# PCB_Headers.net
KiCad netlist of a schematic drawn in Altium Designer
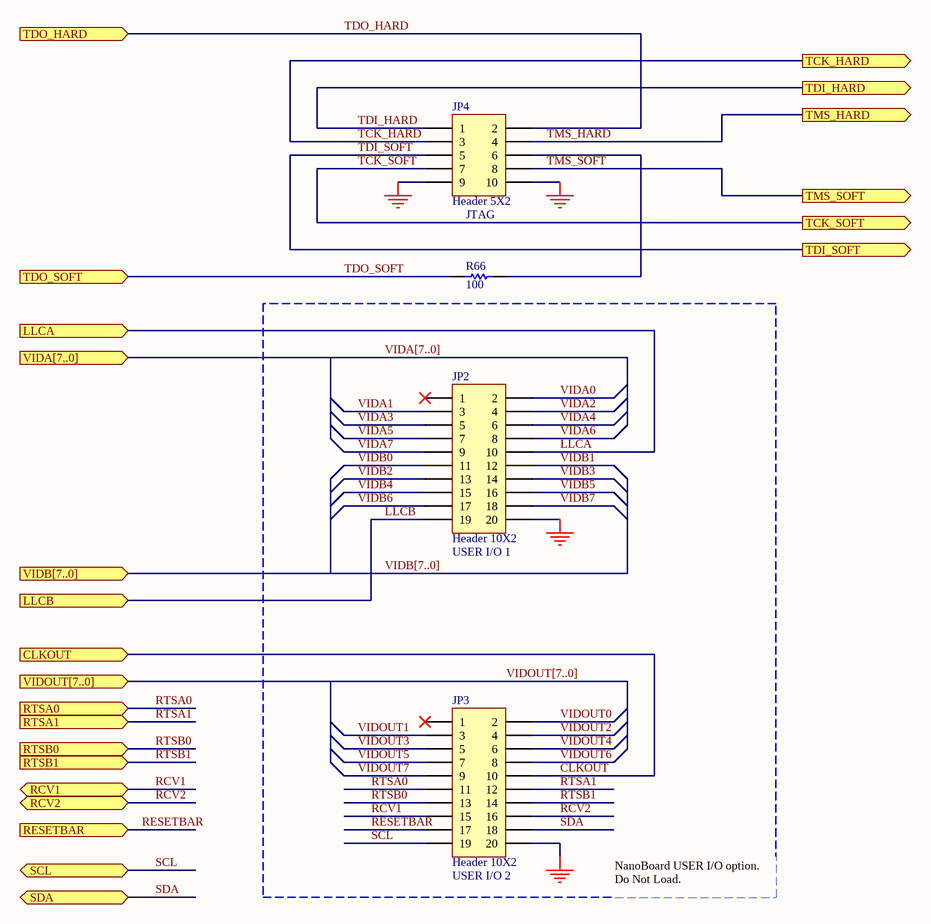
[diagram p0: PCB_Headers.SchDoc]

(export (version "E")
  (design (tool "Eeschema 10.0.6"))
  (components
    (comp (ref "JP2")
      (value "Header 10X2")
      (footprint "HDR2X10")
      (description "Header, 10-Pin, Dual row")
      (fields (field (name "MANUFACTURER") "Generic Components") (field (name "PUBLISHER") "Altium Limited"))
      (libsource (lib "Miscellaneous Connectors") (part "Header 10X2"))
    )
    (comp (ref "JP3")
      (value "Header 10X2")
      (footprint "HDR2X10")
      (description "Header, 10-Pin, Dual row")
      (fields (field (name "MANUFACTURER") "Generic Components") (field (name "PUBLISHER") "Altium Limited"))
      (libsource (lib "Miscellaneous Connectors") (part "Header 10X2"))
    )
    (comp (ref "JP4")
      (value "Header 5X2")
      (footprint "HDR2X5")
      (description "Header, 5-Pin, Dual row")
      (fields (field (name "MANUFACTURER") "Generic Components") (field (name "PUBLISHER") "Altium Limited"))
      (libsource (lib "Miscellaneous Connectors") (part "Header 5X2"))
    )
    (comp (ref "R66")
      (value "100")
      (footprint "PCB_Footprints:CC2012-0805")
      (description "Resistor")
      (libsource (lib "PCB_Symbols") (part "RES"))
    )
  )
  (nets
    (net (code "1") (name "/CLKOUT") (class "Default")
      (node (ref "JP3") (pin "10") (pinfunction "10_10") (pintype "passive"))
    )
    (net (code "2") (name "/LLCA") (class "Default")
      (node (ref "JP2") (pin "10") (pinfunction "10_10") (pintype "passive"))
    )
    (net (code "3") (name "/LLCB") (class "Default")
      (node (ref "JP2") (pin "19") (pinfunction "19_19") (pintype "passive"))
    )
    (net (code "4") (name "/RCV1") (class "Default")
      (node (ref "JP3") (pin "15") (pinfunction "15_15") (pintype "passive"))
    )
    (net (code "5") (name "/RCV2") (class "Default")
      (node (ref "JP3") (pin "16") (pinfunction "16_16") (pintype "passive"))
    )
    (net (code "6") (name "/RESETBAR") (class "Default")
      (node (ref "JP3") (pin "17") (pinfunction "17_17") (pintype "passive"))
    )
    (net (code "7") (name "/RTSA0") (class "Default")
      (node (ref "JP3") (pin "11") (pinfunction "11_11") (pintype "passive"))
    )
    (net (code "8") (name "/RTSA1") (class "Default")
      (node (ref "JP3") (pin "12") (pinfunction "12_12") (pintype "passive"))
    )
    (net (code "9") (name "/RTSB0") (class "Default")
      (node (ref "JP3") (pin "13") (pinfunction "13_13") (pintype "passive"))
    )
    (net (code "10") (name "/RTSB1") (class "Default")
      (node (ref "JP3") (pin "14") (pinfunction "14_14") (pintype "passive"))
    )
    (net (code "11") (name "/SCL") (class "Default")
      (node (ref "JP3") (pin "19") (pinfunction "19_19") (pintype "passive"))
    )
    (net (code "12") (name "/SDA") (class "Default")
      (node (ref "JP3") (pin "18") (pinfunction "18_18") (pintype "passive"))
    )
    (net (code "13") (name "/TCK_HARD") (class "Default")
      (node (ref "JP4") (pin "3") (pinfunction "3_3") (pintype "passive"))
    )
    (net (code "14") (name "/TCK_SOFT") (class "Default")
      (node (ref "JP4") (pin "7") (pinfunction "7_7") (pintype "passive"))
    )
    (net (code "15") (name "/TDI_HARD") (class "Default")
      (node (ref "JP4") (pin "1") (pinfunction "1_1") (pintype "passive"))
    )
    (net (code "16") (name "/TDI_SOFT") (class "Default")
      (node (ref "JP4") (pin "5") (pinfunction "5_5") (pintype "passive"))
    )
    (net (code "17") (name "/TDO_HARD") (class "Default")
      (node (ref "JP4") (pin "2") (pinfunction "2_2") (pintype "passive"))
    )
    (net (code "18") (name "/TDO_SOFT") (class "Default")
      (node (ref "R66") (pin "1") (pinfunction "1_1") (pintype "passive"))
    )
    (net (code "19") (name "/TMS_HARD") (class "Default")
      (node (ref "JP4") (pin "4") (pinfunction "4_4") (pintype "passive"))
    )
    (net (code "20") (name "/TMS_SOFT") (class "Default")
      (node (ref "JP4") (pin "8") (pinfunction "8_8") (pintype "passive"))
    )
    (net (code "21") (name "/VIDA0") (class "Default")
      (node (ref "JP2") (pin "2") (pinfunction "2_2") (pintype "passive"))
    )
    (net (code "22") (name "/VIDA1") (class "Default")
      (node (ref "JP2") (pin "3") (pinfunction "3_3") (pintype "passive"))
    )
    (net (code "23") (name "/VIDA2") (class "Default")
      (node (ref "JP2") (pin "4") (pinfunction "4_4") (pintype "passive"))
    )
    (net (code "24") (name "/VIDA3") (class "Default")
      (node (ref "JP2") (pin "5") (pinfunction "5_5") (pintype "passive"))
    )
    (net (code "25") (name "/VIDA4") (class "Default")
      (node (ref "JP2") (pin "6") (pinfunction "6_6") (pintype "passive"))
    )
    (net (code "26") (name "/VIDA5") (class "Default")
      (node (ref "JP2") (pin "7") (pinfunction "7_7") (pintype "passive"))
    )
    (net (code "27") (name "/VIDA6") (class "Default")
      (node (ref "JP2") (pin "8") (pinfunction "8_8") (pintype "passive"))
    )
    (net (code "28") (name "/VIDA7") (class "Default")
      (node (ref "JP2") (pin "9") (pinfunction "9_9") (pintype "passive"))
    )
    (net (code "30") (name "/VIDB0") (class "Default")
      (node (ref "JP2") (pin "11") (pinfunction "11_11") (pintype "passive"))
    )
    (net (code "31") (name "/VIDB1") (class "Default")
      (node (ref "JP2") (pin "12") (pinfunction "12_12") (pintype "passive"))
    )
    (net (code "32") (name "/VIDB2") (class "Default")
      (node (ref "JP2") (pin "13") (pinfunction "13_13") (pintype "passive"))
    )
    (net (code "33") (name "/VIDB3") (class "Default")
      (node (ref "JP2") (pin "14") (pinfunction "14_14") (pintype "passive"))
    )
    (net (code "34") (name "/VIDB4") (class "Default")
      (node (ref "JP2") (pin "15") (pinfunction "15_15") (pintype "passive"))
    )
    (net (code "35") (name "/VIDB5") (class "Default")
      (node (ref "JP2") (pin "16") (pinfunction "16_16") (pintype "passive"))
    )
    (net (code "36") (name "/VIDB6") (class "Default")
      (node (ref "JP2") (pin "17") (pinfunction "17_17") (pintype "passive"))
    )
    (net (code "37") (name "/VIDB7") (class "Default")
      (node (ref "JP2") (pin "18") (pinfunction "18_18") (pintype "passive"))
    )
    (net (code "39") (name "/VIDOUT0") (class "Default")
      (node (ref "JP3") (pin "2") (pinfunction "2_2") (pintype "passive"))
    )
    (net (code "40") (name "/VIDOUT1") (class "Default")
      (node (ref "JP3") (pin "3") (pinfunction "3_3") (pintype "passive"))
    )
    (net (code "41") (name "/VIDOUT2") (class "Default")
      (node (ref "JP3") (pin "4") (pinfunction "4_4") (pintype "passive"))
    )
    (net (code "42") (name "/VIDOUT3") (class "Default")
      (node (ref "JP3") (pin "5") (pinfunction "5_5") (pintype "passive"))
    )
    (net (code "43") (name "/VIDOUT4") (class "Default")
      (node (ref "JP3") (pin "6") (pinfunction "6_6") (pintype "passive"))
    )
    (net (code "44") (name "/VIDOUT5") (class "Default")
      (node (ref "JP3") (pin "7") (pinfunction "7_7") (pintype "passive"))
    )
    (net (code "45") (name "/VIDOUT6") (class "Default")
      (node (ref "JP3") (pin "8") (pinfunction "8_8") (pintype "passive"))
    )
    (net (code "46") (name "/VIDOUT7") (class "Default")
      (node (ref "JP3") (pin "9") (pinfunction "9_9") (pintype "passive"))
    )
    (net (code "48") (name "GND") (class "Default")
      (node (ref "JP2") (pin "20") (pinfunction "20_20") (pintype "passive"))
      (node (ref "JP3") (pin "20") (pinfunction "20_20") (pintype "passive"))
      (node (ref "JP4") (pin "10") (pinfunction "10_10") (pintype "passive"))
      (node (ref "JP4") (pin "9") (pinfunction "9_9") (pintype "passive"))
    )
    (net (code "49") (name "Net-(JP4-Pad6)") (class "Default")
      (node (ref "JP4") (pin "6") (pinfunction "6_6") (pintype "passive"))
      (node (ref "R66") (pin "2") (pinfunction "2_2") (pintype "passive"))
    )
    (net (code "50") (name "unconnected-(JP2-Pad1)") (class "Default")
      (node (ref "JP2") (pin "1") (pinfunction "1_1") (pintype "passive+no_connect"))
    )
    (net (code "51") (name "unconnected-(JP3-Pad1)") (class "Default")
      (node (ref "JP3") (pin "1") (pinfunction "1_1") (pintype "passive+no_connect"))
    )
  )
)
